# WifiModule.net
KiCad netlist of a schematic drawn in Altium Designer
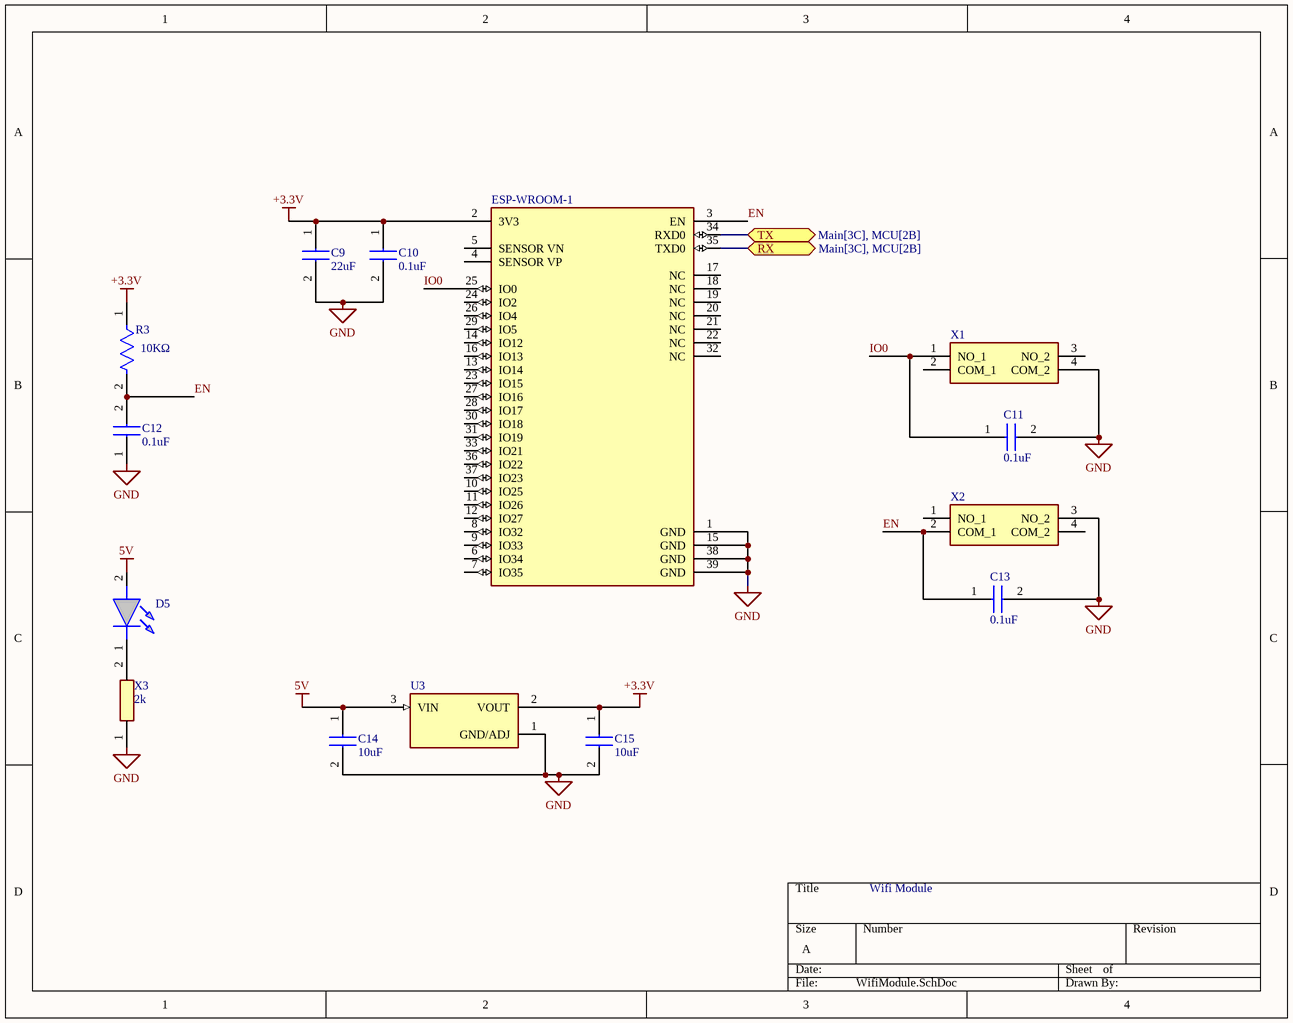
[diagram p0: WifiModule.SchDoc]

(export (version "E")
  (design (tool "Eeschema 10.0.6"))
  (components
    (comp (ref "C9")
      (value "CL31B226KPKVPJE")
      (footprint "CAPC2012X150N")
      (description "General Multilayer Ceramic Capacitors")
      (fields (field (name "MOUSER PART NUMBER") "187-CL31B226KPKVPJE") (field (name "CAPACITAMCE") "22uF"))
      (libsource (lib "Analog_project") (part "CL31B226KPKVPJE"))
    )
    (comp (ref "C10")
      (value "C1206C104K5RAC7867")
      (footprint "CAPC3216X110N")
      (description "Multilayer Ceramic Capacitors MLCC - SMD/SMT 50V 0.1uF X7R 1206 10%")
      (fields (field (name "MOUSER PART NUMBER") "80-C1206104K5RAC7867") (field (name "CAPACITANCE") "0.1uF"))
      (libsource (lib "Analog_project") (part "C1206C104K5RAC7867"))
    )
    (comp (ref "C11")
      (value "C1206C104K5RAC7867")
      (footprint "CAPC3216X110N")
      (description "Multilayer Ceramic Capacitors MLCC - SMD/SMT 50V 0.1uF X7R 1206 10%")
      (fields (field (name "MOUSER PART NUMBER") "80-C1206104K5RAC7867") (field (name "CAPACITANCE") "0.1uF"))
      (libsource (lib "Analog_project") (part "C1206C104K5RAC7867"))
    )
    (comp (ref "C12")
      (value "C1206C104K5RAC7867")
      (footprint "CAPC3216X110N")
      (description "Multilayer Ceramic Capacitors MLCC - SMD/SMT 50V 0.1uF X7R 1206 10%")
      (fields (field (name "MOUSER PART NUMBER") "80-C1206104K5RAC7867") (field (name "CAPACITANCE") "0.1uF"))
      (libsource (lib "Analog_project") (part "C1206C104K5RAC7867"))
    )
    (comp (ref "C13")
      (value "C1206C104K5RAC7867")
      (footprint "CAPC3216X110N")
      (description "Multilayer Ceramic Capacitors MLCC - SMD/SMT 50V 0.1uF X7R 1206 10%")
      (fields (field (name "MOUSER PART NUMBER") "80-C1206104K5RAC7867") (field (name "CAPACITANCE") "0.1uF"))
      (libsource (lib "Analog_project") (part "C1206C104K5RAC7867"))
    )
    (comp (ref "C14")
      (value "C1206C106K8RAC")
      (footprint "CAPC3216X180N")
      (description "Multilayer Ceramic Capacitors MLCC - SMD/SMT 10V 10uF X7R 1206 0.1")
      (fields (field (name "MOUSER PART NUMBER") "80-C1206C106K8RAC") (field (name "CAPACITANCE") "10uF"))
      (libsource (lib "Analog_project") (part "C1206C106K8RAC"))
    )
    (comp (ref "C15")
      (value "C1206C106K8RAC")
      (footprint "CAPC3216X180N")
      (description "Multilayer Ceramic Capacitors MLCC - SMD/SMT 10V 10uF X7R 1206 0.1")
      (fields (field (name "MOUSER PART NUMBER") "80-C1206C106K8RAC") (field (name "CAPACITANCE") "10uF"))
      (libsource (lib "Analog_project") (part "C1206C106K8RAC"))
    )
    (comp (ref "D5")
      (value "150120GS75000")
      (footprint "LEDC3214X78N")
      (fields (field (name "MOUSER PART NUMBER") "710-150120GS75000"))
      (libsource (lib "Analog_project") (part "150120GS75000"))
    )
    (comp (ref "ESP-WROOM-1")
      (value "ESP32-WROOM-32E (16MB)")
      (footprint "FP-ESP32-WROOM-32E_16MB-MFG")
      (description "RX TXRX MOD WIFI TRACE ANT SMD")
      (libsource (lib "Analog_project") (part "CMP-194065-000027-1"))
    )
    (comp (ref "R3")
      (value "10KΩ")
      (footprint "FP-CRGP1210-IPC_A")
      (description "CRGP1210 10KΩ 0.75W ±100ppm/°C 1% 200V")
      (fields
        (field (name "TOLERANCE") "0.01")
        (field (name "OCTOPART") "https://octopart.com/crgp1210f10k-te+connectivity-91018904")
      )
      (libsource (lib "Analog_project") (part "CMP-03211-008532-1"))
    )
    (comp (ref "U3")
      (value "AMS1117-3.3")
      (footprint "SOT229P700X180-4N")
      (description "Sot223/Pkg 1-Amp 3.3-Volt Low Drop Out Voltage Regulatator")
      (fields (field (name "MF") "Advanced Monolithic Systems"))
      (libsource (lib "Analog_project") (part "AMS1117-3.3"))
    )
    (comp (ref "X1")
      (value "TS04-66-65-BK-160-SMT")
      (footprint "TS046665BK160SMT")
      (description "Tactile Switches 6 x 6 mm, 6.5 mm Act Height, 160 gf, Black, Surface Mount, SPST,")
      (fields (field (name "MOUSER PART NUMBER") "179-TS046665BK160SMT"))
      (libsource (lib "Analog_project") (part "TS04-66-65-BK-160-SMT"))
    )
    (comp (ref "X2")
      (value "TS04-66-65-BK-160-SMT")
      (footprint "TS046665BK160SMT")
      (description "Tactile Switches 6 x 6 mm, 6.5 mm Act Height, 160 gf, Black, Surface Mount, SPST,")
      (fields (field (name "MOUSER PART NUMBER") "179-TS046665BK160SMT"))
      (libsource (lib "Analog_project") (part "TS04-66-65-BK-160-SMT"))
    )
    (comp (ref "X3")
      (value "CHP1206AFX-2001ELF")
      (footprint "RESC3116X65X50LL20T20")
      (description "Thick Film Resistors - SMD ResHighPowerA 1206 2k 1% 3/4W TC100 AEC-Q200")
      (fields (field (name "MOUSER PART NUMBER") "652-CHP1206AFX-2001L") (field (name "RESISTANCE") "2k"))
      (libsource (lib "Analog_project") (part "CHP1206AFX-2001ELF"))
    )
  )
  (nets
    (net (code "1") (name "+3.3V") (class "Default")
      (node (ref "C10") (pin "1") (pinfunction "1_1") (pintype "passive"))
      (node (ref "C15") (pin "1") (pinfunction "1_1") (pintype "passive"))
      (node (ref "C9") (pin "1") (pinfunction "1_1") (pintype "passive"))
      (node (ref "ESP-WROOM-1") (pin "2") (pinfunction "3V3_2") (pintype "power_in"))
      (node (ref "R3") (pin "1") (pinfunction "1_1") (pintype "passive"))
      (node (ref "U3") (pin "2") (pinfunction "VOUT_2") (pintype "power_in"))
    )
    (net (code "2") (name "/EN") (class "Default")
      (node (ref "C12") (pin "2") (pinfunction "2_2") (pintype "passive"))
      (node (ref "C13") (pin "1") (pinfunction "1_1") (pintype "passive"))
      (node (ref "ESP-WROOM-1") (pin "3") (pinfunction "EN_3") (pintype "passive"))
      (node (ref "R3") (pin "2") (pinfunction "2_2") (pintype "passive"))
      (node (ref "X2") (pin "2") (pinfunction "COM_1_2") (pintype "passive"))
    )
    (net (code "3") (name "/IO0") (class "Default")
      (node (ref "C11") (pin "1") (pinfunction "1_1") (pintype "passive"))
      (node (ref "ESP-WROOM-1") (pin "25") (pinfunction "IO0_25") (pintype "bidirectional"))
      (node (ref "X1") (pin "1") (pinfunction "NO_1_1") (pintype "passive"))
    )
    (net (code "4") (name "/RX") (class "Default")
      (node (ref "ESP-WROOM-1") (pin "35") (pinfunction "TXD0_35") (pintype "bidirectional"))
    )
    (net (code "5") (name "/TX") (class "Default")
      (node (ref "ESP-WROOM-1") (pin "34") (pinfunction "RXD0_34") (pintype "bidirectional"))
    )
    (net (code "6") (name "5V") (class "Default")
      (node (ref "C14") (pin "1") (pinfunction "1_1") (pintype "passive"))
      (node (ref "D5") (pin "2") (pinfunction "A_2") (pintype "passive"))
      (node (ref "U3") (pin "3") (pinfunction "VIN_3") (pintype "input"))
    )
    (net (code "7") (name "GND") (class "Default")
      (node (ref "C10") (pin "2") (pinfunction "2_2") (pintype "passive"))
      (node (ref "C11") (pin "2") (pinfunction "2_2") (pintype "passive"))
      (node (ref "C12") (pin "1") (pinfunction "1_1") (pintype "passive"))
      (node (ref "C13") (pin "2") (pinfunction "2_2") (pintype "passive"))
      (node (ref "C14") (pin "2") (pinfunction "2_2") (pintype "passive"))
      (node (ref "C15") (pin "2") (pinfunction "2_2") (pintype "passive"))
      (node (ref "C9") (pin "2") (pinfunction "2_2") (pintype "passive"))
      (node (ref "ESP-WROOM-1") (pin "1") (pinfunction "GND_1") (pintype "power_in"))
      (node (ref "ESP-WROOM-1") (pin "15") (pinfunction "GND_15") (pintype "power_in"))
      (node (ref "ESP-WROOM-1") (pin "38") (pinfunction "GND_38") (pintype "power_in"))
      (node (ref "ESP-WROOM-1") (pin "39") (pinfunction "GND_39") (pintype "power_in"))
      (node (ref "U3") (pin "1") (pinfunction "GND/ADJ_1") (pintype "power_in"))
      (node (ref "X1") (pin "4") (pinfunction "COM_2_4") (pintype "passive"))
      (node (ref "X2") (pin "3") (pinfunction "NO_2_3") (pintype "passive"))
      (node (ref "X3") (pin "1") (pinfunction "1_1") (pintype "passive"))
    )
    (net (code "8") (name "Net-(D5-K)") (class "Default")
      (node (ref "D5") (pin "1") (pinfunction "K_1") (pintype "passive"))
      (node (ref "X3") (pin "2") (pinfunction "2_2") (pintype "passive"))
    )
    (net (code "9") (name "unconnected-(ESP-WROOM-1-IO2-Pad24)") (class "Default")
      (node (ref "ESP-WROOM-1") (pin "24") (pinfunction "IO2_24") (pintype "bidirectional"))
    )
    (net (code "10") (name "unconnected-(ESP-WROOM-1-IO4-Pad26)") (class "Default")
      (node (ref "ESP-WROOM-1") (pin "26") (pinfunction "IO4_26") (pintype "bidirectional"))
    )
    (net (code "11") (name "unconnected-(ESP-WROOM-1-IO5-Pad29)") (class "Default")
      (node (ref "ESP-WROOM-1") (pin "29") (pinfunction "IO5_29") (pintype "bidirectional"))
    )
    (net (code "12") (name "unconnected-(ESP-WROOM-1-IO12-Pad14)") (class "Default")
      (node (ref "ESP-WROOM-1") (pin "14") (pinfunction "IO12_14") (pintype "bidirectional"))
    )
    (net (code "13") (name "unconnected-(ESP-WROOM-1-IO13-Pad16)") (class "Default")
      (node (ref "ESP-WROOM-1") (pin "16") (pinfunction "IO13_16") (pintype "bidirectional"))
    )
    (net (code "14") (name "unconnected-(ESP-WROOM-1-IO14-Pad13)") (class "Default")
      (node (ref "ESP-WROOM-1") (pin "13") (pinfunction "IO14_13") (pintype "bidirectional"))
    )
    (net (code "15") (name "unconnected-(ESP-WROOM-1-IO15-Pad23)") (class "Default")
      (node (ref "ESP-WROOM-1") (pin "23") (pinfunction "IO15_23") (pintype "bidirectional"))
    )
    (net (code "16") (name "unconnected-(ESP-WROOM-1-IO16-Pad27)") (class "Default")
      (node (ref "ESP-WROOM-1") (pin "27") (pinfunction "IO16_27") (pintype "bidirectional"))
    )
    (net (code "17") (name "unconnected-(ESP-WROOM-1-IO17-Pad28)") (class "Default")
      (node (ref "ESP-WROOM-1") (pin "28") (pinfunction "IO17_28") (pintype "bidirectional"))
    )
    (net (code "18") (name "unconnected-(ESP-WROOM-1-IO18-Pad30)") (class "Default")
      (node (ref "ESP-WROOM-1") (pin "30") (pinfunction "IO18_30") (pintype "bidirectional"))
    )
    (net (code "19") (name "unconnected-(ESP-WROOM-1-IO19-Pad31)") (class "Default")
      (node (ref "ESP-WROOM-1") (pin "31") (pinfunction "IO19_31") (pintype "bidirectional"))
    )
    (net (code "20") (name "unconnected-(ESP-WROOM-1-IO21-Pad33)") (class "Default")
      (node (ref "ESP-WROOM-1") (pin "33") (pinfunction "IO21_33") (pintype "bidirectional"))
    )
    (net (code "21") (name "unconnected-(ESP-WROOM-1-IO22-Pad36)") (class "Default")
      (node (ref "ESP-WROOM-1") (pin "36") (pinfunction "IO22_36") (pintype "bidirectional"))
    )
    (net (code "22") (name "unconnected-(ESP-WROOM-1-IO23-Pad37)") (class "Default")
      (node (ref "ESP-WROOM-1") (pin "37") (pinfunction "IO23_37") (pintype "bidirectional"))
    )
    (net (code "23") (name "unconnected-(ESP-WROOM-1-IO25-Pad10)") (class "Default")
      (node (ref "ESP-WROOM-1") (pin "10") (pinfunction "IO25_10") (pintype "bidirectional"))
    )
    (net (code "24") (name "unconnected-(ESP-WROOM-1-IO26-Pad11)") (class "Default")
      (node (ref "ESP-WROOM-1") (pin "11") (pinfunction "IO26_11") (pintype "bidirectional"))
    )
    (net (code "25") (name "unconnected-(ESP-WROOM-1-IO27-Pad12)") (class "Default")
      (node (ref "ESP-WROOM-1") (pin "12") (pinfunction "IO27_12") (pintype "bidirectional"))
    )
    (net (code "26") (name "unconnected-(ESP-WROOM-1-IO32-Pad8)") (class "Default")
      (node (ref "ESP-WROOM-1") (pin "8") (pinfunction "IO32_8") (pintype "bidirectional"))
    )
    (net (code "27") (name "unconnected-(ESP-WROOM-1-IO33-Pad9)") (class "Default")
      (node (ref "ESP-WROOM-1") (pin "9") (pinfunction "IO33_9") (pintype "bidirectional"))
    )
    (net (code "28") (name "unconnected-(ESP-WROOM-1-IO34-Pad6)") (class "Default")
      (node (ref "ESP-WROOM-1") (pin "6") (pinfunction "IO34_6") (pintype "bidirectional"))
    )
    (net (code "29") (name "unconnected-(ESP-WROOM-1-IO35-Pad7)") (class "Default")
      (node (ref "ESP-WROOM-1") (pin "7") (pinfunction "IO35_7") (pintype "bidirectional"))
    )
    (net (code "30") (name "unconnected-(ESP-WROOM-1-NC-Pad17)") (class "Default")
      (node (ref "ESP-WROOM-1") (pin "17") (pinfunction "NC_17") (pintype "passive"))
    )
    (net (code "31") (name "unconnected-(ESP-WROOM-1-NC-Pad18)") (class "Default")
      (node (ref "ESP-WROOM-1") (pin "18") (pinfunction "NC_18") (pintype "passive"))
    )
    (net (code "32") (name "unconnected-(ESP-WROOM-1-NC-Pad19)") (class "Default")
      (node (ref "ESP-WROOM-1") (pin "19") (pinfunction "NC_19") (pintype "passive"))
    )
    (net (code "33") (name "unconnected-(ESP-WROOM-1-NC-Pad20)") (class "Default")
      (node (ref "ESP-WROOM-1") (pin "20") (pinfunction "NC_20") (pintype "passive"))
    )
    (net (code "34") (name "unconnected-(ESP-WROOM-1-NC-Pad21)") (class "Default")
      (node (ref "ESP-WROOM-1") (pin "21") (pinfunction "NC_21") (pintype "passive"))
    )
    (net (code "35") (name "unconnected-(ESP-WROOM-1-NC-Pad22)") (class "Default")
      (node (ref "ESP-WROOM-1") (pin "22") (pinfunction "NC_22") (pintype "passive"))
    )
    (net (code "36") (name "unconnected-(ESP-WROOM-1-NC-Pad32)") (class "Default")
      (node (ref "ESP-WROOM-1") (pin "32") (pinfunction "NC_32") (pintype "passive"))
    )
    (net (code "37") (name "unconnected-(ESP-WROOM-1-SENSOR_VN-Pad5)") (class "Default")
      (node (ref "ESP-WROOM-1") (pin "5") (pinfunction "SENSOR_VN_5") (pintype "passive"))
    )
    (net (code "38") (name "unconnected-(ESP-WROOM-1-SENSOR_VP-Pad4)") (class "Default")
      (node (ref "ESP-WROOM-1") (pin "4") (pinfunction "SENSOR_VP_4") (pintype "passive"))
    )
    (net (code "39") (name "unconnected-(X1-COM_1-Pad2)") (class "Default")
      (node (ref "X1") (pin "2") (pinfunction "COM_1_2") (pintype "passive"))
    )
    (net (code "40") (name "unconnected-(X1-NO_2-Pad3)") (class "Default")
      (node (ref "X1") (pin "3") (pinfunction "NO_2_3") (pintype "passive"))
    )
    (net (code "41") (name "unconnected-(X2-COM_2-Pad4)") (class "Default")
      (node (ref "X2") (pin "4") (pinfunction "COM_2_4") (pintype "passive"))
    )
    (net (code "42") (name "unconnected-(X2-NO_1-Pad1)") (class "Default")
      (node (ref "X2") (pin "1") (pinfunction "NO_1_1") (pintype "passive"))
    )
  )
)
